# Power.net
KiCad netlist of a schematic drawn in Altium Designer
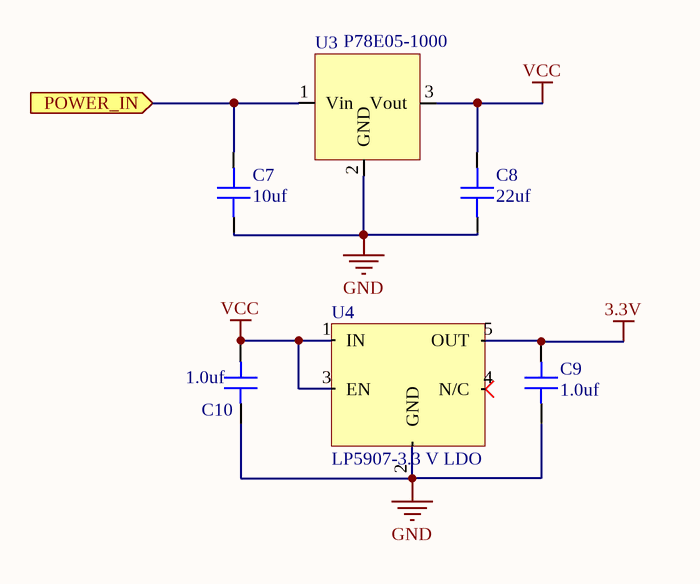
[diagram p0: Power.SchDoc]

(export (version "E")
  (design (tool "Eeschema 10.0.6"))
  (components
    (comp (ref "C7")
      (value "10uf")
      (footprint "CAP 1206/3216 - 1.8MM")
      (fields
        (field (name "Comment") "Capacitor MLCC 1.1pf 50V CAP 1206/3216")
        (field (name "CREATED_BY") "Nick Mah")
      )
      (libsource (lib "") (part "Capacitor_1"))
    )
    (comp (ref "C8")
      (value "22uf")
      (footprint "CAP 0805/2012")
      (fields
        (field (name "Comment") "Capacitor MLCC 22uf 16V CAP 0805/2012")
        (field (name "CREATED_BY") "Nick Mah")
      )
      (libsource (lib "") (part "Capacitor_1"))
    )
    (comp (ref "C9")
      (value "1.0uf")
      (footprint "CAP 0603/1608")
      (fields
        (field (name "Comment") "Capacitor MLCC 1.0uf 16V CAP 0603/1608")
        (field (name "CREATED_BY") "Nick Mah")
      )
      (libsource (lib "Altium-Lib") (part "Capacitor"))
    )
    (comp (ref "C10")
      (value "1.0uf")
      (footprint "CAP 0603/1608")
      (fields
        (field (name "Comment") "Capacitor MLCC 1.0uf 16V CAP 0603/1608")
        (field (name "CREATED_BY") "Nick Mah")
      )
      (libsource (lib "Altium-Lib") (part "Capacitor"))
    )
    (comp (ref "U3")
      (value "P78E05-1000")
      (footprint "P78E05")
      (description "Non-Isolated PoL Module DC DC Converter 1 Output 5V    1A 8V - 36V Input")
      (fields (field (name "POWER") "5W") (field (name "CREATED_BY") "Nick"))
      (libsource (lib "Altium-Lib") (part "P78E05"))
    )
    (comp (ref "U4")
      (value "LP5907-3.3 V LDO")
      (footprint "SOT23-5")
      (fields (field (name "MFRPARTNO") "LP5907"))
      (libsource (lib "Altium-Lib") (part "LP5907-3.3 V LDO"))
    )
  )
  (nets
    (net (code "1") (name "/POWER_IN") (class "Default")
      (node (ref "C7") (pin "2") (pinfunction "2_2") (pintype "passive"))
      (node (ref "U3") (pin "1") (pinfunction "Vin_1") (pintype "power_in"))
    )
    (net (code "2") (name "3.3V") (class "Default")
      (node (ref "C9") (pin "2") (pinfunction "2_2") (pintype "passive"))
      (node (ref "U4") (pin "5") (pinfunction "OUT_5") (pintype "input"))
    )
    (net (code "3") (name "GND") (class "Default")
      (node (ref "C10") (pin "1") (pinfunction "1_1") (pintype "passive"))
      (node (ref "C7") (pin "1") (pinfunction "1_1") (pintype "passive"))
      (node (ref "C8") (pin "1") (pinfunction "1_1") (pintype "passive"))
      (node (ref "C9") (pin "1") (pinfunction "1_1") (pintype "passive"))
      (node (ref "U3") (pin "2") (pinfunction "GND_2") (pintype "power_in"))
      (node (ref "U4") (pin "2") (pinfunction "GND_2") (pintype "input"))
    )
    (net (code "4") (name "VCC") (class "Default")
      (node (ref "C10") (pin "2") (pinfunction "2_2") (pintype "passive"))
      (node (ref "C8") (pin "2") (pinfunction "2_2") (pintype "passive"))
      (node (ref "U3") (pin "3") (pinfunction "Vout_3") (pintype "power_in"))
      (node (ref "U4") (pin "1") (pinfunction "IN_1") (pintype "input"))
      (node (ref "U4") (pin "3") (pinfunction "EN_3") (pintype "input"))
    )
    (net (code "5") (name "unconnected-(U4-N{slash}C-Pad4)") (class "Default")
      (node (ref "U4") (pin "4") (pinfunction "N/C_4") (pintype "input+no_connect"))
    )
  )
)
